# ConnectionsAndPower.net
KiCad netlist of a schematic drawn in Altium Designer
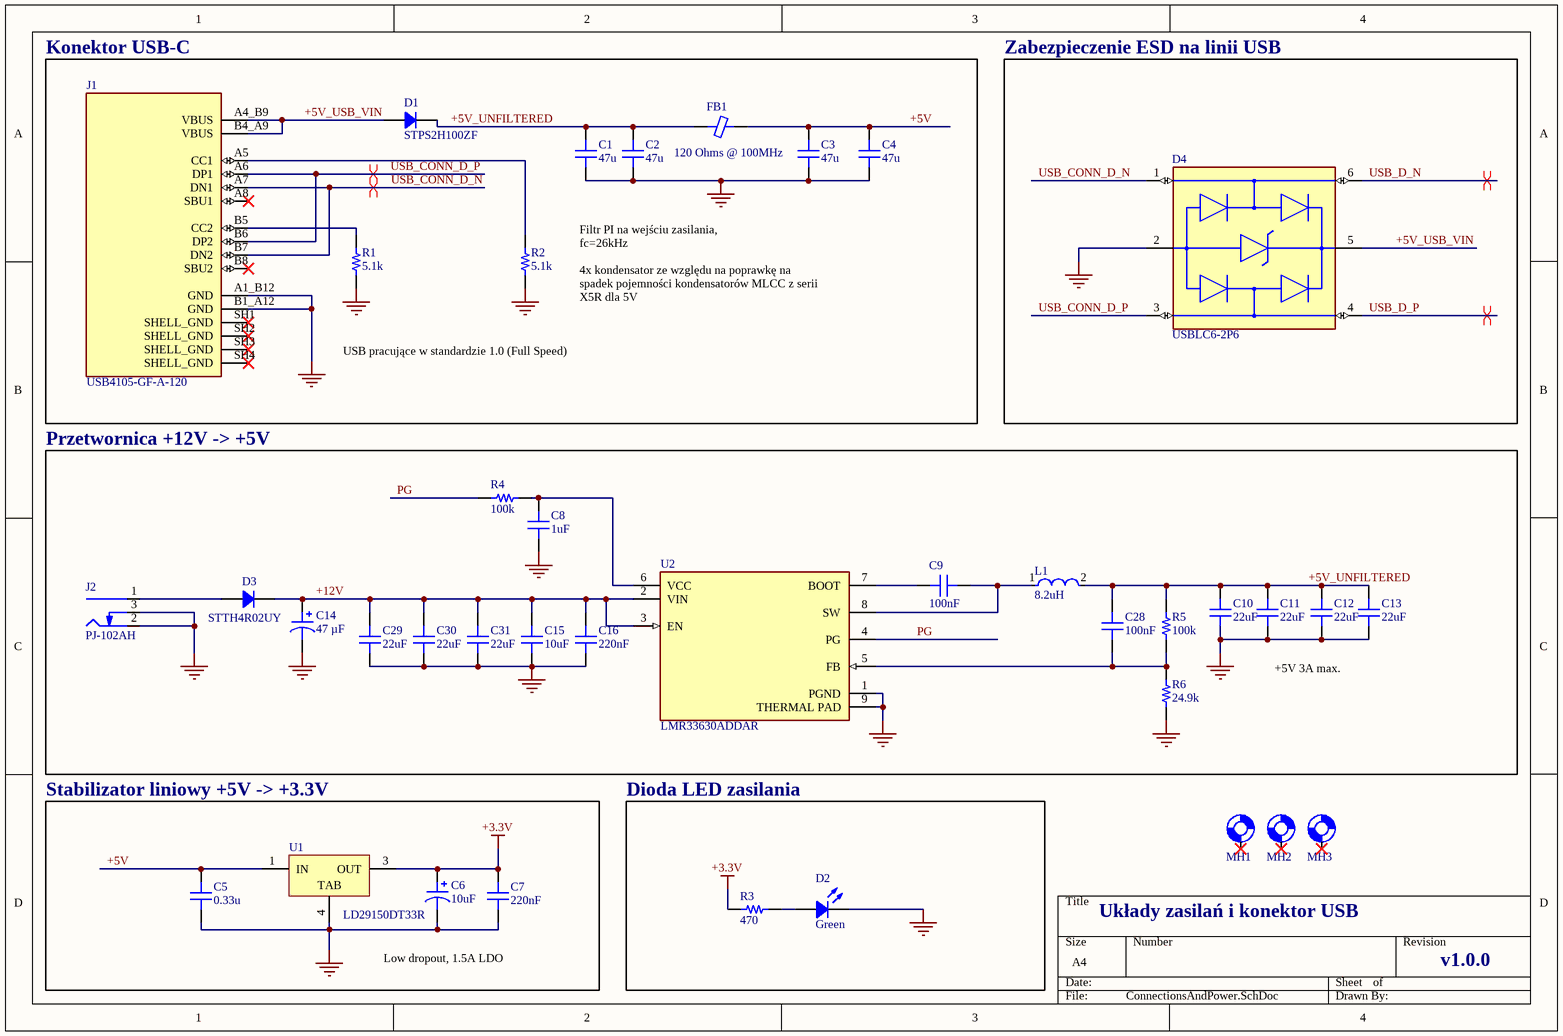
[diagram p0: ConnectionsAndPower.SchDoc]

(export (version "E")
  (design (tool "Eeschema 10.0.6"))
  (components
    (comp (ref "C1")
      (value "47 µF")
      (footprint "CAP 0805_2012")
      (description "CAP CER 47UF 6.3V X5R 0805")
      (fields
        (field (name "PART NUMBER") "CL21A476MQYNNNE")
        (field (name "CAPACITANCE") "47u")
        (field (name "MANUFACTURER") "Samsung Electro-Mechanics")
      )
      (libsource (lib "Celestial Altium Library - altium_library") (part "Capacitor"))
    )
    (comp (ref "C2")
      (value "47 µF")
      (footprint "CAP 0805_2012")
      (description "CAP CER 47UF 6.3V X5R 0805")
      (fields
        (field (name "PART NUMBER") "CL21A476MQYNNNE")
        (field (name "CAPACITANCE") "47u")
        (field (name "MANUFACTURER") "Samsung Electro-Mechanics")
      )
      (libsource (lib "Celestial Altium Library - altium_library") (part "Capacitor"))
    )
    (comp (ref "C3")
      (value "47 µF")
      (footprint "CAP 0805_2012")
      (description "CAP CER 47UF 6.3V X5R 0805")
      (fields
        (field (name "PART NUMBER") "CL21A476MQYNNNE")
        (field (name "CAPACITANCE") "47u")
        (field (name "MANUFACTURER") "Samsung Electro-Mechanics")
      )
      (libsource (lib "Celestial Altium Library - altium_library") (part "Capacitor"))
    )
    (comp (ref "C4")
      (value "47 µF")
      (footprint "CAP 0805_2012")
      (description "CAP CER 47UF 6.3V X5R 0805")
      (fields
        (field (name "PART NUMBER") "CL21A476MQYNNNE")
        (field (name "CAPACITANCE") "47u")
        (field (name "MANUFACTURER") "Samsung Electro-Mechanics")
      )
      (libsource (lib "Celestial Altium Library - altium_library") (part "Capacitor"))
    )
    (comp (ref "C5")
      (value "0.33µF")
      (footprint "CAP 0805_2012")
      (description "CAP CER 0.33UF 50V X7R 0805")
      (fields
        (field (name "PART NUMBER") "08055C334JAT2A")
        (field (name "CAPACITANCE") "0.33u")
        (field (name "MANUFACTURER") "AVX Corporation")
      )
      (libsource (lib "Celestial Altium Library - altium_library") (part "Capacitor"))
    )
    (comp (ref "C6")
      (value "10uF")
      (footprint "CAP ALSMD POLY 4.3MM H5.5MM")
      (description "CAP ALUM POLY 10UF 20% 10V SMD")
      (fields
        (field (name "PART NUMBER") "10SVP10M")
        (field (name "MANUFACTURER") "Panasonic Electronic Components")
      )
      (libsource (lib "Celestial Altium Library - altium_library") (part "Polarised Capacitor"))
    )
    (comp (ref "C7")
      (value "0.22 µF")
      (footprint "CAP 0805_2012")
      (description "CAP CER 0805 220NF 100V X7R 5%")
      (fields
        (field (name "PART NUMBER") "C0805C224J1REC7800")
        (field (name "CAPACITANCE") "220nF")
        (field (name "MANUFACTURER") "KEMET")
      )
      (libsource (lib "Celestial Altium Library - altium_library") (part "Capacitor"))
    )
    (comp (ref "C8")
      (value "1µF")
      (footprint "CAP 0805_2012")
      (description "CAP CER 1UF 50V X7R 0805")
      (fields
        (field (name "PART NUMBER") "08055C105K4Z2A")
        (field (name "CAPACITANCE") "1uF")
        (field (name "MANUFACTURER") "AVX Corporation")
      )
      (libsource (lib "Celestial Altium Library - altium_library") (part "Capacitor"))
    )
    (comp (ref "C9")
      (value "0.1 µF")
      (footprint "CAP 0805_2012")
      (description "CAP CER 0.1UF 50V X7R 0805")
      (fields
        (field (name "PART NUMBER") "CC0805MRX7R9BB104")
        (field (name "CAPACITANCE") "100nF")
        (field (name "MANUFACTURER") "Yageo")
      )
      (libsource (lib "Celestial Altium Library - altium_library") (part "Capacitor"))
    )
    (comp (ref "C10")
      (value "22 µF")
      (footprint "CAP 0805_2012")
      (description "CAP CER 22UF 16V X5R 0805")
      (fields
        (field (name "PART NUMBER") "CL21A226KOQNNNE")
        (field (name "CAPACITANCE") "22uF")
        (field (name "MANUFACTURER") "Samsung Electro-Mechanics")
      )
      (libsource (lib "Celestial Altium Library - altium_library") (part "Capacitor"))
    )
    (comp (ref "C11")
      (value "22 µF")
      (footprint "CAP 0805_2012")
      (description "CAP CER 22UF 16V X5R 0805")
      (fields
        (field (name "PART NUMBER") "CL21A226KOQNNNE")
        (field (name "CAPACITANCE") "22uF")
        (field (name "MANUFACTURER") "Samsung Electro-Mechanics")
      )
      (libsource (lib "Celestial Altium Library - altium_library") (part "Capacitor"))
    )
    (comp (ref "C12")
      (value "22 µF")
      (footprint "CAP 0805_2012")
      (description "CAP CER 22UF 16V X5R 0805")
      (fields
        (field (name "PART NUMBER") "CL21A226KOQNNNE")
        (field (name "CAPACITANCE") "22uF")
        (field (name "MANUFACTURER") "Samsung Electro-Mechanics")
      )
      (libsource (lib "Celestial Altium Library - altium_library") (part "Capacitor"))
    )
    (comp (ref "C13")
      (value "22 µF")
      (footprint "CAP 0805_2012")
      (description "CAP CER 22UF 16V X5R 0805")
      (fields
        (field (name "PART NUMBER") "CL21A226KOQNNNE")
        (field (name "CAPACITANCE") "22uF")
        (field (name "MANUFACTURER") "Samsung Electro-Mechanics")
      )
      (libsource (lib "Celestial Altium Library - altium_library") (part "Capacitor"))
    )
    (comp (ref "C14")
      (value "47 µF")
      (footprint "CAP ALSMD 4.3MM H5.4MM")
      (description "CAP ALUM 47UF 20% 6.3V SMD")
      (fields
        (field (name "PART NUMBER") "EMVA6R3ADA470MD55G")
        (field (name "MANUFACTURER") "United Chemi-Con")
      )
      (libsource (lib "Celestial Altium Library - altium_library") (part "Polarised Capacitor"))
    )
    (comp (ref "C15")
      (value "10 µF")
      (footprint "CAP 0805_2012")
      (description "CAP CER 10UF 16V X6S 0805")
      (fields
        (field (name "PART NUMBER") "C2012X6S1C106K125AC")
        (field (name "CAPACITANCE") "10uF")
        (field (name "MANUFACTURER") "TDK Corporation")
      )
      (libsource (lib "Celestial Altium Library - altium_library") (part "Capacitor"))
    )
    (comp (ref "C16")
      (value "0.22 µF")
      (footprint "CAP 0805_2012")
      (description "CAP CER 0805 220NF 100V X7R 5%")
      (fields
        (field (name "PART NUMBER") "C0805C224J1REC7800")
        (field (name "CAPACITANCE") "220nF")
        (field (name "MANUFACTURER") "KEMET")
      )
      (libsource (lib "Celestial Altium Library - altium_library") (part "Capacitor"))
    )
    (comp (ref "C28")
      (value "0.1 µF")
      (footprint "CAP 0603_1608")
      (description "CAP CER 0.1UF 25V X7R 0603")
      (fields
        (field (name "PART NUMBER") "CL10B104KA8NNNC")
        (field (name "CAPACITANCE") "100nF")
        (field (name "MANUFACTURER") "Samsung Electro-Mechanics")
      )
      (libsource (lib "Celestial Altium Library - altium_library") (part "Capacitor"))
    )
    (comp (ref "C29")
      (value "22 µF")
      (footprint "CAP 0805_2012")
      (description "CAP CER 22UF 16V X5R 0805")
      (fields
        (field (name "PART NUMBER") "CL21A226KOQNNNE")
        (field (name "CAPACITANCE") "22uF")
        (field (name "MANUFACTURER") "Samsung Electro-Mechanics")
      )
      (libsource (lib "Celestial Altium Library - altium_library") (part "Capacitor"))
    )
    (comp (ref "C30")
      (value "22 µF")
      (footprint "CAP 0805_2012")
      (description "CAP CER 22UF 16V X5R 0805")
      (fields
        (field (name "PART NUMBER") "CL21A226KOQNNNE")
        (field (name "CAPACITANCE") "22uF")
        (field (name "MANUFACTURER") "Samsung Electro-Mechanics")
      )
      (libsource (lib "Celestial Altium Library - altium_library") (part "Capacitor"))
    )
    (comp (ref "C31")
      (value "22 µF")
      (footprint "CAP 0805_2012")
      (description "CAP CER 22UF 16V X5R 0805")
      (fields
        (field (name "PART NUMBER") "CL21A226KOQNNNE")
        (field (name "CAPACITANCE") "22uF")
        (field (name "MANUFACTURER") "Samsung Electro-Mechanics")
      )
      (libsource (lib "Celestial Altium Library - altium_library") (part "Capacitor"))
    )
    (comp (ref "D1")
      (value "STPS2H100ZF")
      (footprint "SOD123F")
      (description "DIODE SCHOTTKY 100V 2A SOD123F")
      (fields (field (name "MANUFACTURER") "STMicroelectronics"))
      (libsource (lib "Celestial Altium Library - altium_library") (part "Diode"))
    )
    (comp (ref "D2")
      (value "Green")
      (footprint "LED 0805_2012 GREEN")
      (description "LED GREEN CLEAR CHIP SMD")
      (fields (field (name "PART NUMBER") "APHCM2012CGCK-F01") (field (name "MANUFACTURER") "Kingbright"))
      (libsource (lib "Celestial Altium Library - altium_library") (part "LED"))
    )
    (comp (ref "D3")
      (value "STTH4R02UY")
      (footprint "DO214AA SMB")
      (description "DIODE GEN PURP 200V 4A SMB")
      (fields (field (name "MANUFACTURER") "STMicroelectronics"))
      (libsource (lib "Celestial Altium Library - altium_library") (part "Diode"))
    )
    (comp (ref "D4")
      (value "USBLC6-2P6")
      (footprint "FP-SOT-666-MFG")
      (description "TVS DIODE 5.25V 17V SOT666")
      (libsource (lib "Altium Content Vault") (part "c871e55f7e3243d341edbd671b98d92"))
    )
    (comp (ref "FB1")
      (value "120 Ohms @ 100MHz")
      (footprint "FER 0805_2012")
      (description "EMI BEAD FILETER")
      (fields
        (field (name "PART NUMBER") "BBUP00201209121Y00")
        (field (name "MANUFACTURER") "Chilisin Electronics")
      )
      (libsource (lib "Celestial Altium Library - altium_library") (part "Ferrite Chip"))
    )
    (comp (ref "J1")
      (value "USB4105-GF-A-120")
      (footprint "USB4105-GF-A-120")
      (description "USB C socket; SMT; PIN: 16; top board mount; 5A")
      (libsource (lib "My_sockets") (part "USB4105-GF-A-120"))
    )
    (comp (ref "J2")
      (value "PJ-102AH")
      (footprint "CUI PJ-102AH")
      (description "CONN PWR JACK 2X5.5MM SOLDER")
      (fields (field (name "MANUFACTURER") "CUI Devices"))
      (libsource (lib "Celestial Altium Library - altium_library") (part "Barrel Connector"))
    )
    (comp (ref "L1")
      (value "8.2uH")
      (footprint "FP-IHLP-2525CZ-FP_2_413x3-MFG")
      (description "Commercial Inductors, High Saturation Series 8.2uH 4A 68mΩ 20%")
      (fields (field (name "TOLERANCE") "20%"))
      (libsource (lib "Altium Content Vault") (part "725321dda6339637d4d059423bc1c3c"))
    )
    (comp (ref "MH1")
      (value "M3 Mounting Hole")
      (footprint "M3_MOUNTING_HOLE")
      (libsource (lib "Mounting_components") (part "M3 Mounting Hole"))
    )
    (comp (ref "MH2")
      (value "M3 Mounting Hole")
      (footprint "M3_MOUNTING_HOLE")
      (libsource (lib "Mounting_components") (part "M3 Mounting Hole"))
    )
    (comp (ref "MH3")
      (value "M3 Mounting Hole")
      (footprint "M3_MOUNTING_HOLE")
      (libsource (lib "Mounting_components") (part "M3 Mounting Hole"))
    )
    (comp (ref "R1")
      (value "5.1k")
      (footprint "RES 0805_2012")
      (description "RES SMD 5.1K OHM 0.5% 1/8W 0805")
      (fields
        (field (name "PART NUMBER") "ERA-6AED512V")
        (field (name "MANUFACTURER") "Panasonic Electronic Components")
      )
      (libsource (lib "Celestial Altium Library - altium_library") (part "Resistor"))
    )
    (comp (ref "R2")
      (value "5.1k")
      (footprint "RES 0805_2012")
      (description "RES SMD 5.1K OHM 0.5% 1/8W 0805")
      (fields
        (field (name "PART NUMBER") "ERA-6AED512V")
        (field (name "MANUFACTURER") "Panasonic Electronic Components")
      )
      (libsource (lib "Celestial Altium Library - altium_library") (part "Resistor"))
    )
    (comp (ref "R3")
      (value "470")
      (footprint "RES 0805_2012")
      (description "RES 470 OHM 1% 1/3W 0805")
      (fields
        (field (name "PART NUMBER") "CRGP0805F470R")
        (field (name "MANUFACTURER") "TE Connectivity Passive Product")
      )
      (libsource (lib "Celestial Altium Library - altium_library") (part "Resistor"))
    )
    (comp (ref "R4")
      (value "100k")
      (footprint "RES 0805_2012")
      (description "RES SMD 100K OHM 0.1% 1/10W 0805")
      (fields
        (field (name "PART NUMBER") "CPF0805B100KE")
        (field (name "MANUFACTURER") "TE Connectivity Passive Product")
      )
      (libsource (lib "Celestial Altium Library - altium_library") (part "Resistor"))
    )
    (comp (ref "R5")
      (value "100k")
      (footprint "RES 0805_2012")
      (description "RES SMD 100K OHM 0.1% 1/10W 0805")
      (fields
        (field (name "PART NUMBER") "CPF0805B100KE")
        (field (name "MANUFACTURER") "TE Connectivity Passive Product")
      )
      (libsource (lib "Celestial Altium Library - altium_library") (part "Resistor"))
    )
    (comp (ref "R6")
      (value "24.9k")
      (footprint "RES 0805_2012")
      (description "RES SMD 24.9K OHM 0.5% 1/4W 0805")
      (fields
        (field (name "PART NUMBER") "RNCF0805DTE24K9")
        (field (name "MANUFACTURER") "Stackpole Electronics Inc")
      )
      (libsource (lib "Celestial Altium Library - altium_library") (part "Resistor"))
    )
    (comp (ref "U1")
      (value "LD29150DT33R")
      (footprint "TO-252_L")
      (description "1.5A, Very-Low Drop Voltage Regulator, 3.3V, 3-Pin DPAK")
      (libsource (lib "Altium Content Vault") (part "PM-REG-LD29150-SOT3"))
    )
    (comp (ref "U2")
      (value "LMR33630ADDAR")
      (footprint "FP-DDA0008J-IPC_B")
      (description "IC REG BUCK ADJUSTABLE 3A 8SOPWR")
      (libsource (lib "Altium Content Vault") (part "6a354f5098e7f60ae670b755afcc2ec"))
    )
  )
  (nets
    (net (code "1") (name "+3.3V") (class "Default")
      (node (ref "C6") (pin "1") (pinfunction "1_1") (pintype "passive"))
      (node (ref "C7") (pin "2") (pinfunction "2_2") (pintype "passive"))
      (node (ref "R3") (pin "1") (pinfunction "1_1") (pintype "passive"))
      (node (ref "U1") (pin "3") (pinfunction "OUT_3") (pintype "power_in"))
    )
    (net (code "2") (name "/+5V") (class "Default")
      (node (ref "C3") (pin "2") (pinfunction "2_2") (pintype "passive"))
      (node (ref "C4") (pin "2") (pinfunction "2_2") (pintype "passive"))
      (node (ref "C5") (pin "2") (pinfunction "2_2") (pintype "passive"))
      (node (ref "FB1") (pin "2") (pinfunction "2_2") (pintype "passive"))
      (node (ref "U1") (pin "1") (pinfunction "IN_1") (pintype "power_in"))
    )
    (net (code "3") (name "/+5V_UNFILTERED") (class "Default")
      (node (ref "C1") (pin "2") (pinfunction "2_2") (pintype "passive"))
      (node (ref "C10") (pin "2") (pinfunction "2_2") (pintype "passive"))
      (node (ref "C11") (pin "2") (pinfunction "2_2") (pintype "passive"))
      (node (ref "C12") (pin "2") (pinfunction "2_2") (pintype "passive"))
      (node (ref "C13") (pin "2") (pinfunction "2_2") (pintype "passive"))
      (node (ref "C2") (pin "2") (pinfunction "2_2") (pintype "passive"))
      (node (ref "C28") (pin "2") (pinfunction "2_2") (pintype "passive"))
      (node (ref "D1") (pin "2") (pinfunction "2_2") (pintype "passive"))
      (node (ref "FB1") (pin "1") (pinfunction "1_1") (pintype "passive"))
      (node (ref "L1") (pin "2") (pinfunction "2_2") (pintype "passive"))
      (node (ref "R5") (pin "1") (pinfunction "1_1") (pintype "passive"))
    )
    (net (code "4") (name "/+5V_USB_VIN") (class "Default")
      (node (ref "D1") (pin "1") (pinfunction "1_1") (pintype "passive"))
      (node (ref "D4") (pin "5") (pinfunction "VBUS_5") (pintype "power_in"))
      (node (ref "J1") (pin "A4_B9") (pinfunction "VBUS_A4_B9") (pintype "power_in"))
      (node (ref "J1") (pin "B4_A9") (pinfunction "VBUS_B4_A9") (pintype "power_in"))
    )
    (net (code "5") (name "/+12V") (class "Default")
      (node (ref "C14") (pin "1") (pinfunction "1_1") (pintype "passive"))
      (node (ref "C15") (pin "2") (pinfunction "2_2") (pintype "passive"))
      (node (ref "C16") (pin "2") (pinfunction "2_2") (pintype "passive"))
      (node (ref "C29") (pin "2") (pinfunction "2_2") (pintype "passive"))
      (node (ref "C30") (pin "2") (pinfunction "2_2") (pintype "passive"))
      (node (ref "C31") (pin "2") (pinfunction "2_2") (pintype "passive"))
      (node (ref "D3") (pin "2") (pinfunction "2_2") (pintype "passive"))
      (node (ref "U2") (pin "2") (pinfunction "VIN_2") (pintype "power_in"))
      (node (ref "U2") (pin "3") (pinfunction "EN_3") (pintype "input"))
    )
    (net (code "6") (name "/PG") (class "Default")
      (node (ref "R4") (pin "2") (pinfunction "2_2") (pintype "passive"))
      (node (ref "U2") (pin "4") (pinfunction "PG_4") (pintype "open_collector"))
    )
    (net (code "7") (name "/USB_CONN_D_N") (class "Default")
      (node (ref "D4") (pin "1") (pinfunction "I/O1_1") (pintype "bidirectional"))
      (node (ref "J1") (pin "A7") (pinfunction "DN1_A7") (pintype "bidirectional"))
      (node (ref "J1") (pin "B7") (pinfunction "DN2_B7") (pintype "bidirectional"))
    )
    (net (code "8") (name "/USB_CONN_D_P") (class "Default")
      (node (ref "D4") (pin "3") (pinfunction "I/O2_3") (pintype "bidirectional"))
      (node (ref "J1") (pin "A6") (pinfunction "DP1_A6") (pintype "bidirectional"))
      (node (ref "J1") (pin "B6") (pinfunction "DP2_B6") (pintype "bidirectional"))
    )
    (net (code "9") (name "/USB_D_N") (class "Default")
      (node (ref "D4") (pin "6") (pinfunction "I/O1_6") (pintype "bidirectional"))
    )
    (net (code "10") (name "/USB_D_P") (class "Default")
      (node (ref "D4") (pin "4") (pinfunction "I/O2_4") (pintype "bidirectional"))
    )
    (net (code "11") (name "GND") (class "Default")
      (node (ref "C1") (pin "1") (pinfunction "1_1") (pintype "passive"))
      (node (ref "C10") (pin "1") (pinfunction "1_1") (pintype "passive"))
      (node (ref "C11") (pin "1") (pinfunction "1_1") (pintype "passive"))
      (node (ref "C12") (pin "1") (pinfunction "1_1") (pintype "passive"))
      (node (ref "C13") (pin "1") (pinfunction "1_1") (pintype "passive"))
      (node (ref "C14") (pin "2") (pinfunction "2_2") (pintype "passive"))
      (node (ref "C15") (pin "1") (pinfunction "1_1") (pintype "passive"))
      (node (ref "C16") (pin "1") (pinfunction "1_1") (pintype "passive"))
      (node (ref "C2") (pin "1") (pinfunction "1_1") (pintype "passive"))
      (node (ref "C29") (pin "1") (pinfunction "1_1") (pintype "passive"))
      (node (ref "C3") (pin "1") (pinfunction "1_1") (pintype "passive"))
      (node (ref "C30") (pin "1") (pinfunction "1_1") (pintype "passive"))
      (node (ref "C31") (pin "1") (pinfunction "1_1") (pintype "passive"))
      (node (ref "C4") (pin "1") (pinfunction "1_1") (pintype "passive"))
      (node (ref "C5") (pin "1") (pinfunction "1_1") (pintype "passive"))
      (node (ref "C6") (pin "2") (pinfunction "2_2") (pintype "passive"))
      (node (ref "C7") (pin "1") (pinfunction "1_1") (pintype "passive"))
      (node (ref "C8") (pin "1") (pinfunction "1_1") (pintype "passive"))
      (node (ref "D2") (pin "2") (pinfunction "2_2") (pintype "passive"))
      (node (ref "D4") (pin "2") (pinfunction "GND_2") (pintype "power_in"))
      (node (ref "J1") (pin "A1_B12") (pinfunction "GND_A1_B12") (pintype "power_in"))
      (node (ref "J1") (pin "B1_A12") (pinfunction "GND_B1_A12") (pintype "power_in"))
      (node (ref "J2") (pin "2") (pinfunction "Outer_2") (pintype "passive"))
      (node (ref "J2") (pin "3") (pinfunction "SW_3") (pintype "passive"))
      (node (ref "R1") (pin "1") (pinfunction "1_1") (pintype "passive"))
      (node (ref "R2") (pin "1") (pinfunction "1_1") (pintype "passive"))
      (node (ref "R6") (pin "1") (pinfunction "1_1") (pintype "passive"))
      (node (ref "U1") (pin "4") (pinfunction "TAB_4") (pintype "passive"))
      (node (ref "U2") (pin "1") (pinfunction "PGND_1") (pintype "power_in"))
      (node (ref "U2") (pin "9") (pinfunction "THERMAL_PAD_9") (pintype "passive"))
    )
    (net (code "12") (name "Net-(D2-Pad1)") (class "Default")
      (node (ref "D2") (pin "1") (pinfunction "1_1") (pintype "passive"))
      (node (ref "R3") (pin "2") (pinfunction "2_2") (pintype "passive"))
    )
    (net (code "13") (name "Net-(J1-CC1)") (class "Default")
      (node (ref "J1") (pin "A5") (pinfunction "CC1_A5") (pintype "bidirectional"))
      (node (ref "R2") (pin "2") (pinfunction "2_2") (pintype "passive"))
    )
    (net (code "14") (name "Net-(J1-CC2)") (class "Default")
      (node (ref "J1") (pin "B5") (pinfunction "CC2_B5") (pintype "bidirectional"))
      (node (ref "R1") (pin "2") (pinfunction "2_2") (pintype "passive"))
    )
    (net (code "15") (name "Net-(J2-Centre)") (class "Default")
      (node (ref "D3") (pin "1") (pinfunction "1_1") (pintype "passive"))
      (node (ref "J2") (pin "1") (pinfunction "Centre_1") (pintype "passive"))
    )
    (net (code "16") (name "Net-(U2-BOOT)") (class "Default")
      (node (ref "C9") (pin "2") (pinfunction "2_2") (pintype "passive"))
      (node (ref "U2") (pin "7") (pinfunction "BOOT_7") (pintype "passive"))
    )
    (net (code "17") (name "Net-(U2-FB)") (class "Default")
      (node (ref "C28") (pin "1") (pinfunction "1_1") (pintype "passive"))
      (node (ref "R5") (pin "2") (pinfunction "2_2") (pintype "passive"))
      (node (ref "R6") (pin "2") (pinfunction "2_2") (pintype "passive"))
      (node (ref "U2") (pin "5") (pinfunction "FB_5") (pintype "input"))
    )
    (net (code "18") (name "Net-(U2-SW)") (class "Default")
      (node (ref "C9") (pin "1") (pinfunction "1_1") (pintype "passive"))
      (node (ref "L1") (pin "1") (pinfunction "1_1") (pintype "passive"))
      (node (ref "U2") (pin "8") (pinfunction "SW_8") (pintype "passive"))
    )
    (net (code "19") (name "Net-(U2-VCC)") (class "Default")
      (node (ref "C8") (pin "2") (pinfunction "2_2") (pintype "passive"))
      (node (ref "R4") (pin "1") (pinfunction "1_1") (pintype "passive"))
      (node (ref "U2") (pin "6") (pinfunction "VCC_6") (pintype "power_in"))
    )
    (net (code "20") (name "unconnected-(J1-SBU1-PadA8)") (class "Default")
      (node (ref "J1") (pin "A8") (pinfunction "SBU1_A8") (pintype "bidirectional+no_connect"))
    )
    (net (code "21") (name "unconnected-(J1-SBU2-PadB8)") (class "Default")
      (node (ref "J1") (pin "B8") (pinfunction "SBU2_B8") (pintype "bidirectional+no_connect"))
    )
    (net (code "22") (name "unconnected-(J1-SHELL_GND-PadSH1)") (class "Default")
      (node (ref "J1") (pin "SH1") (pinfunction "SHELL_GND_SH1") (pintype "power_in+no_connect"))
    )
    (net (code "23") (name "unconnected-(J1-SHELL_GND-PadSH2)") (class "Default")
      (node (ref "J1") (pin "SH2") (pinfunction "SHELL_GND_SH2") (pintype "power_in+no_connect"))
    )
    (net (code "24") (name "unconnected-(J1-SHELL_GND-PadSH3)") (class "Default")
      (node (ref "J1") (pin "SH3") (pinfunction "SHELL_GND_SH3") (pintype "power_in+no_connect"))
    )
    (net (code "25") (name "unconnected-(J1-SHELL_GND-PadSH4)") (class "Default")
      (node (ref "J1") (pin "SH4") (pinfunction "SHELL_GND_SH4") (pintype "power_in+no_connect"))
    )
    (net (code "26") (name "unconnected-(MH1-Pad1)") (class "Default")
      (node (ref "MH1") (pin "1") (pinfunction "1_1") (pintype "passive+no_connect"))
    )
    (net (code "27") (name "unconnected-(MH2-Pad1)") (class "Default")
      (node (ref "MH2") (pin "1") (pinfunction "1_1") (pintype "passive+no_connect"))
    )
    (net (code "28") (name "unconnected-(MH3-Pad1)") (class "Default")
      (node (ref "MH3") (pin "1") (pinfunction "1_1") (pintype "passive+no_connect"))
    )
  )
)
